# Skematic.net
KiCad netlist of a schematic drawn in EasyEDA
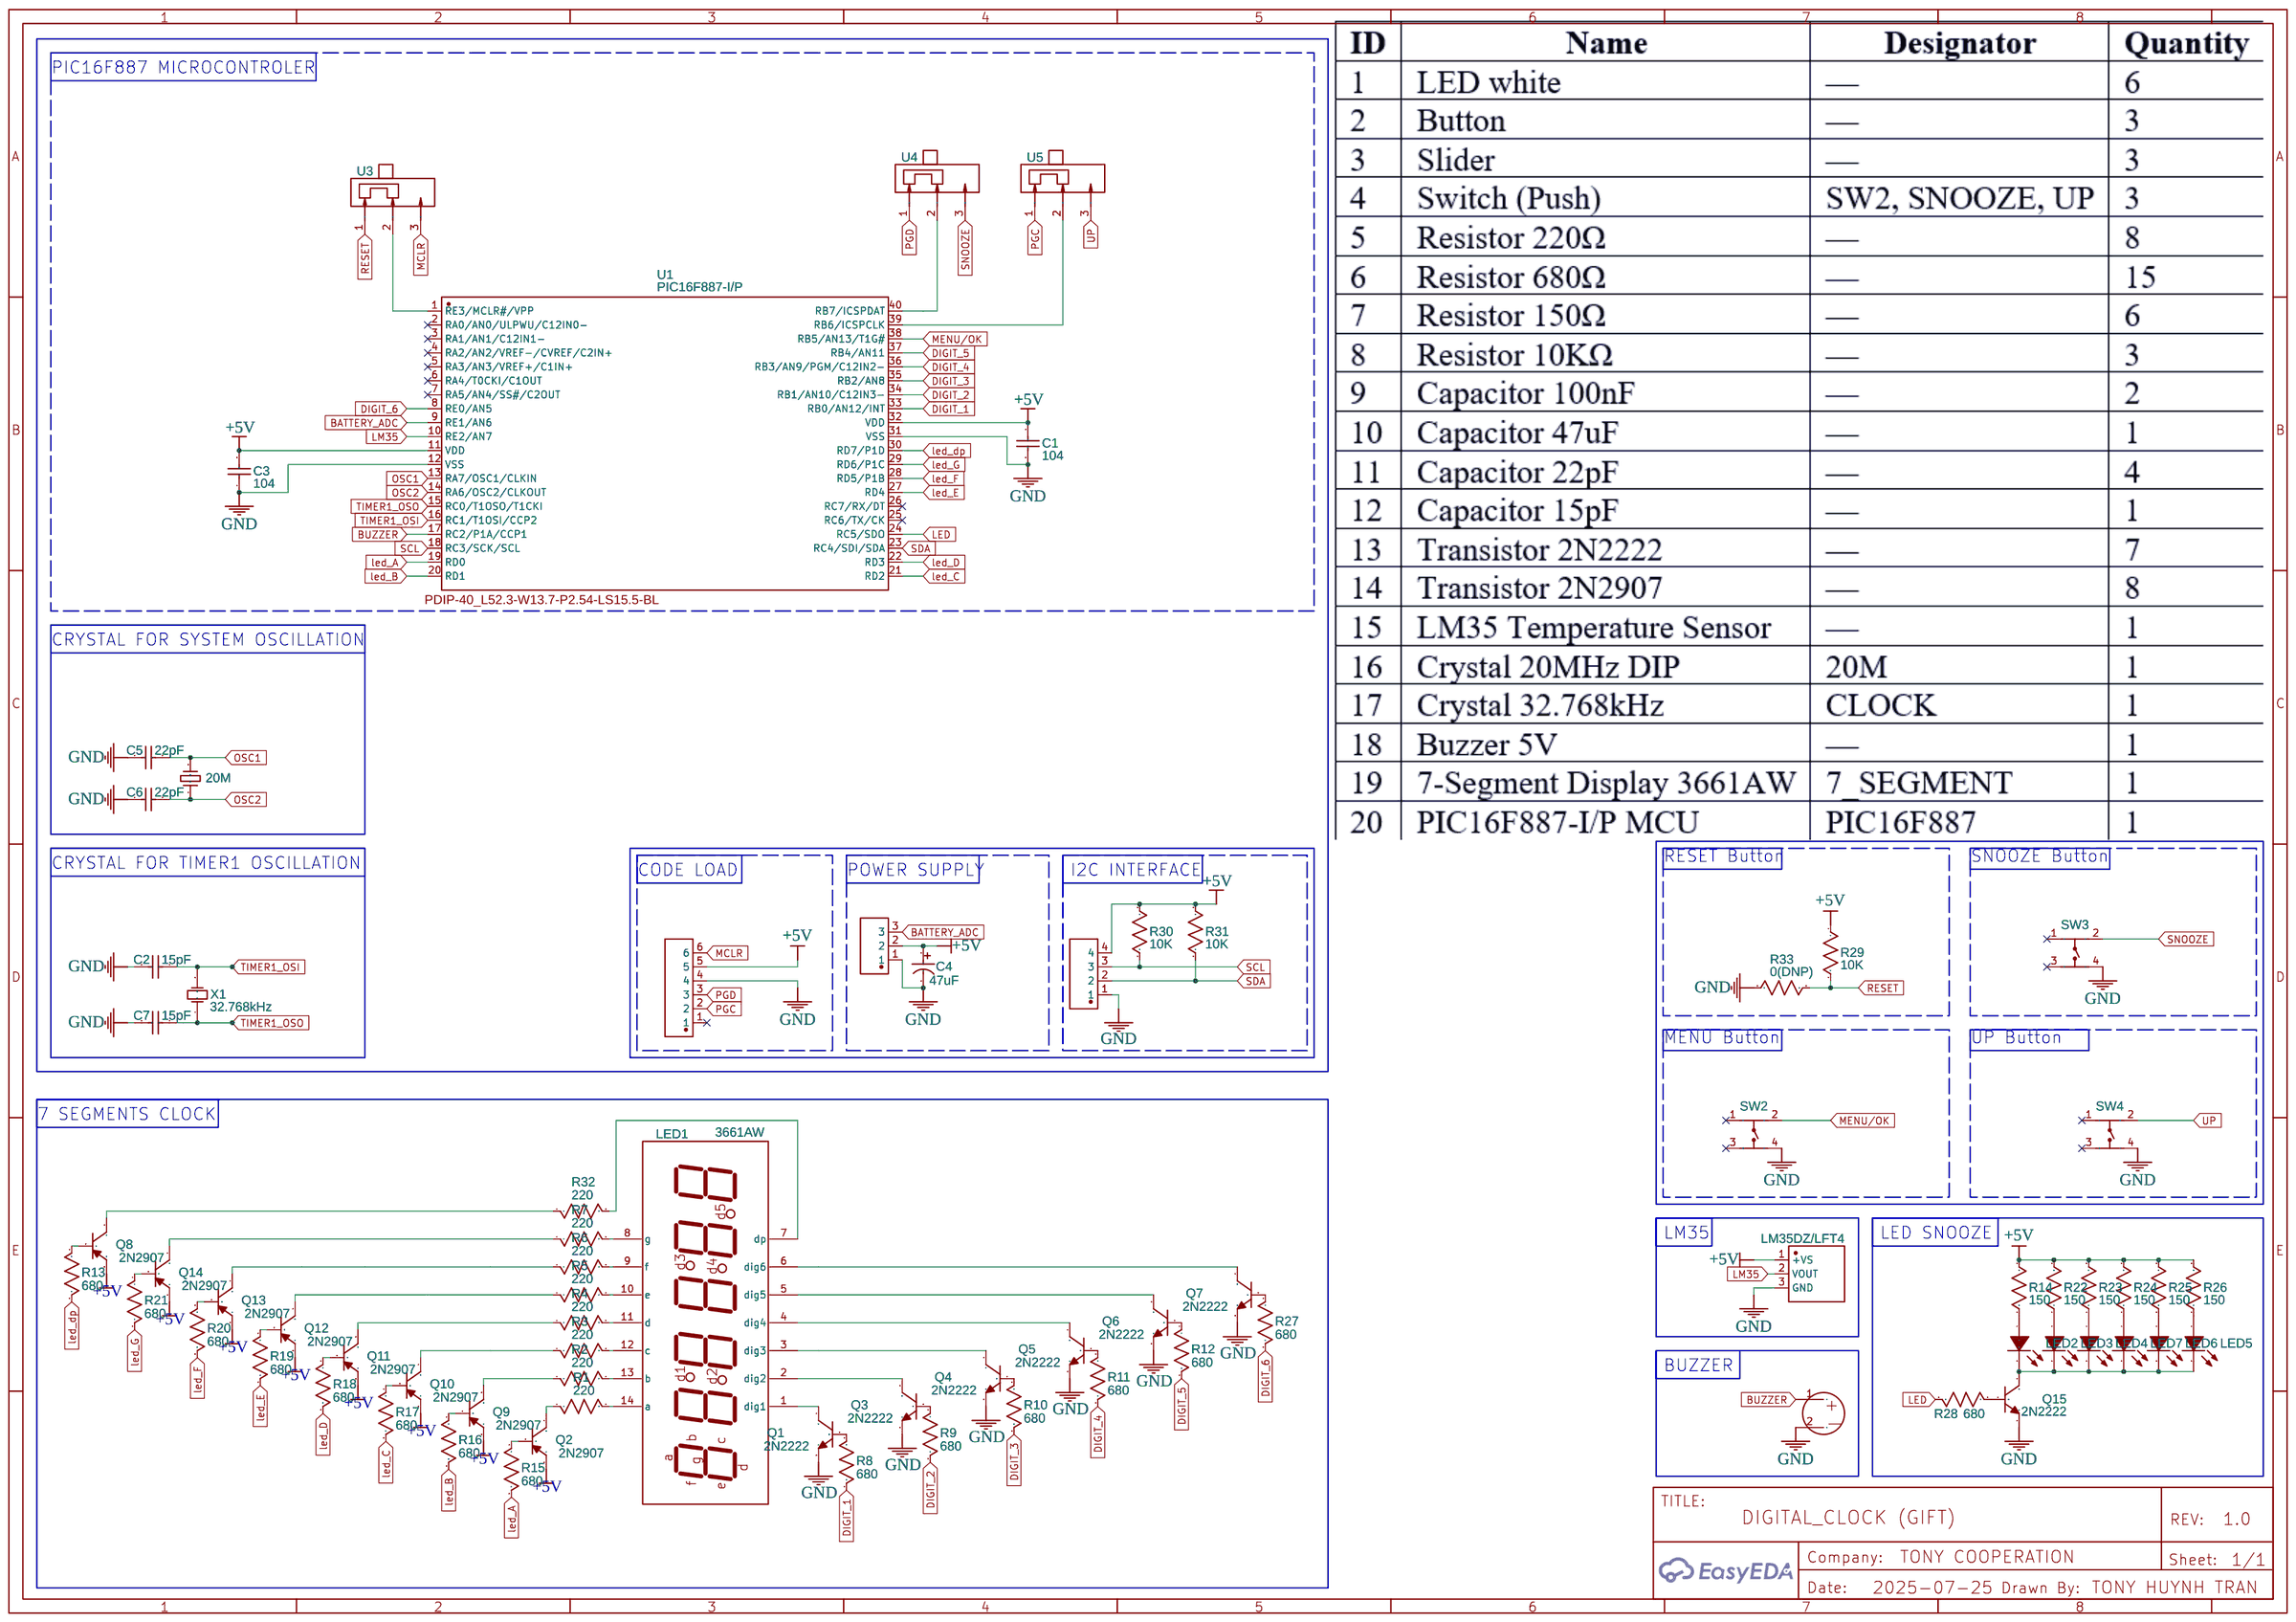
[diagram p0: schematic sheet]

(export (version "E")
  (design (tool "Eeschema 10.0.6"))
  (components
    (comp (ref "20M") (value "Crystal DIP 5.08mm") (libsource (lib "") (part "Crystal DIP 5.08mm")))
    (comp (ref "C1")
      (value "104")
      (fields
        (field (name "Manufacturer Part") "Suppression Capacitor222M/250V")
        (field (name "Manufacturer") "ReliaPro")
      )
      (libsource (lib "") (part "CAP-104"))
    )
    (comp (ref "C2")
      (value "15pF")
      (fields (field (name "Manufacturer Part") "22pf/50V 10%") (field (name "Manufacturer") "ReliaPro"))
      (libsource (lib "") (part "22pF"))
    )
    (comp (ref "C3")
      (value "104")
      (fields
        (field (name "Manufacturer Part") "Suppression Capacitor222M/250V")
        (field (name "Manufacturer") "ReliaPro")
      )
      (libsource (lib "") (part "CAP-104"))
    )
    (comp (ref "C4")
      (value "47uF")
      (fields
        (field (name "Manufacturer Part") "KM108M025G17RR0VH2FP0")
        (field (name "Manufacturer") "CX(承兴)")
      )
      (libsource (lib "") (part "16V 47UF COPY"))
    )
    (comp (ref "C5")
      (value "22pF")
      (fields (field (name "Manufacturer Part") "22pf/50V 10%") (field (name "Manufacturer") "ReliaPro"))
      (libsource (lib "") (part "22pF"))
    )
    (comp (ref "C6")
      (value "22pF")
      (fields (field (name "Manufacturer Part") "22pf/50V 10%") (field (name "Manufacturer") "ReliaPro"))
      (libsource (lib "") (part "22pF"))
    )
    (comp (ref "C7")
      (value "15pF")
      (fields (field (name "Manufacturer Part") "22pf/50V 10%") (field (name "Manufacturer") "ReliaPro"))
      (libsource (lib "") (part "22pF"))
    )
    (comp (ref "H1")
      (value "HC-PZ200-8.7L-1X4PZ")
      (fields
        (field (name "Manufacturer Part") "HC-PZ200-8.7L-1x4PZ")
        (field (name "Manufacturer") "HC(虹成电子)")
      )
      (libsource (lib "") (part "HC-PZ200-8.7L-1X4PZ"))
    )
    (comp (ref "H2")
      (value "HX PZ1.27-1X6P WZ")
      (fields
        (field (name "Manufacturer Part") "HX PZ1.27-1x6P WZ")
        (field (name "Manufacturer") "hanxia(韩下)")
      )
      (libsource (lib "") (part "HX PZ1.27-1X6P WZ"))
    )
    (comp (ref "H3")
      (value "HX PZ2.0-1X3P WZ-AM")
      (fields
        (field (name "Manufacturer Part") "HX PZ2.0-1x3P WZ-AM")
        (field (name "Manufacturer") "hanxia(韩下)")
      )
      (libsource (lib "") (part "HX PZ2.0-1X3P WZ-AM"))
    )
    (comp (ref "LED1")
      (value "3661AW")
      (fields (field (name "Manufacturer Part") "3661A_CLK") (field (name "Manufacturer") "CLee LED Store"))
      (libsource (lib "") (part "3661A_CLK"))
    )
    (comp (ref "LED2")
      (value "LED-TH-5mm_R")
      (fields
        (field (name "Manufacturer Part") "333-2SURD/S530-A3")
        (field (name "Manufacturer") "EVERLIGHT(台湾亿光)")
      )
      (libsource (lib "") (part "LED-TH-5mm_R"))
    )
    (comp (ref "LED3")
      (value "LED-TH-5mm_R")
      (fields
        (field (name "Manufacturer Part") "333-2SURD/S530-A3")
        (field (name "Manufacturer") "EVERLIGHT(台湾亿光)")
      )
      (libsource (lib "") (part "LED-TH-5mm_R"))
    )
    (comp (ref "LED4")
      (value "LED-TH-5mm_R")
      (fields
        (field (name "Manufacturer Part") "333-2SURD/S530-A3")
        (field (name "Manufacturer") "EVERLIGHT(台湾亿光)")
      )
      (libsource (lib "") (part "LED-TH-5mm_R"))
    )
    (comp (ref "LED5")
      (value "LED-TH-5mm_R")
      (fields
        (field (name "Manufacturer Part") "333-2SURD/S530-A3")
        (field (name "Manufacturer") "EVERLIGHT(台湾亿光)")
      )
      (libsource (lib "") (part "LED-TH-5mm_R"))
    )
    (comp (ref "LED6")
      (value "LED-TH-5mm_R")
      (fields
        (field (name "Manufacturer Part") "333-2SURD/S530-A3")
        (field (name "Manufacturer") "EVERLIGHT(台湾亿光)")
      )
      (libsource (lib "") (part "LED-TH-5mm_R"))
    )
    (comp (ref "LED7")
      (value "LED-TH-5mm_R")
      (fields
        (field (name "Manufacturer Part") "333-2SURD/S530-A3")
        (field (name "Manufacturer") "EVERLIGHT(台湾亿光)")
      )
      (libsource (lib "") (part "LED-TH-5mm_R"))
    )
    (comp (ref "Q1")
      (value "2N2222")
      (fields (field (name "Manufacturer Part") "2N2222A") (field (name "Manufacturer") "BLUE ROCKET(蓝箭)"))
      (libsource (lib "") (part "2N2222A"))
    )
    (comp (ref "Q2")
      (value "2N2907")
      (fields (field (name "Manufacturer Part") "2N2907A") (field (name "Manufacturer") "BLUE ROCKET(蓝箭)"))
      (libsource (lib "") (part "2N2907A"))
    )
    (comp (ref "Q3")
      (value "2N2222")
      (fields (field (name "Manufacturer Part") "2N2222A") (field (name "Manufacturer") "BLUE ROCKET(蓝箭)"))
      (libsource (lib "") (part "2N2222A"))
    )
    (comp (ref "Q4")
      (value "2N2222")
      (fields (field (name "Manufacturer Part") "2N2222A") (field (name "Manufacturer") "BLUE ROCKET(蓝箭)"))
      (libsource (lib "") (part "2N2222A"))
    )
    (comp (ref "Q5")
      (value "2N2222")
      (fields (field (name "Manufacturer Part") "2N2222A") (field (name "Manufacturer") "BLUE ROCKET(蓝箭)"))
      (libsource (lib "") (part "2N2222A"))
    )
    (comp (ref "Q6")
      (value "2N2222")
      (fields (field (name "Manufacturer Part") "2N2222A") (field (name "Manufacturer") "BLUE ROCKET(蓝箭)"))
      (libsource (lib "") (part "2N2222A"))
    )
    (comp (ref "Q7")
      (value "2N2222")
      (fields (field (name "Manufacturer Part") "2N2222A") (field (name "Manufacturer") "BLUE ROCKET(蓝箭)"))
      (libsource (lib "") (part "2N2222A"))
    )
    (comp (ref "Q8")
      (value "2N2907")
      (fields (field (name "Manufacturer Part") "2N2907A") (field (name "Manufacturer") "BLUE ROCKET(蓝箭)"))
      (libsource (lib "") (part "2N2907A"))
    )
    (comp (ref "Q9")
      (value "2N2907")
      (fields (field (name "Manufacturer Part") "2N2907A") (field (name "Manufacturer") "BLUE ROCKET(蓝箭)"))
      (libsource (lib "") (part "2N2907A"))
    )
    (comp (ref "Q10")
      (value "2N2907")
      (fields (field (name "Manufacturer Part") "2N2907A") (field (name "Manufacturer") "BLUE ROCKET(蓝箭)"))
      (libsource (lib "") (part "2N2907A"))
    )
    (comp (ref "Q11")
      (value "2N2907")
      (fields (field (name "Manufacturer Part") "2N2907A") (field (name "Manufacturer") "BLUE ROCKET(蓝箭)"))
      (libsource (lib "") (part "2N2907A"))
    )
    (comp (ref "Q12")
      (value "2N2907")
      (fields (field (name "Manufacturer Part") "2N2907A") (field (name "Manufacturer") "BLUE ROCKET(蓝箭)"))
      (libsource (lib "") (part "2N2907A"))
    )
    (comp (ref "Q13")
      (value "2N2907")
      (fields (field (name "Manufacturer Part") "2N2907A") (field (name "Manufacturer") "BLUE ROCKET(蓝箭)"))
      (libsource (lib "") (part "2N2907A"))
    )
    (comp (ref "Q14")
      (value "2N2907")
      (fields (field (name "Manufacturer Part") "2N2907A") (field (name "Manufacturer") "BLUE ROCKET(蓝箭)"))
      (libsource (lib "") (part "2N2907A"))
    )
    (comp (ref "Q15")
      (value "2N2222")
      (fields (field (name "Manufacturer Part") "2N2222A") (field (name "Manufacturer") "BLUE ROCKET(蓝箭)"))
      (libsource (lib "") (part "2N2222A_1"))
    )
    (comp (ref "R1") (value "220") (libsource (lib "") (part "R_AXIAL-0.4_US_3")))
    (comp (ref "R2") (value "220") (libsource (lib "") (part "R_AXIAL-0.4_US_3")))
    (comp (ref "R3") (value "220") (libsource (lib "") (part "R_AXIAL-0.4_US_3")))
    (comp (ref "R4") (value "220") (libsource (lib "") (part "R_AXIAL-0.4_US_3")))
    (comp (ref "R5") (value "220") (libsource (lib "") (part "R_AXIAL-0.4_US_3")))
    (comp (ref "R6") (value "220") (libsource (lib "") (part "R_AXIAL-0.4_US_3")))
    (comp (ref "R7") (value "220") (libsource (lib "") (part "R_AXIAL-0.4_US_3")))
    (comp (ref "R8") (value "680") (libsource (lib "") (part "R_AXIAL-0.4_US_2")))
    (comp (ref "R9") (value "680") (libsource (lib "") (part "R_AXIAL-0.4_US_2")))
    (comp (ref "R10") (value "680") (libsource (lib "") (part "R_AXIAL-0.4_US_2")))
    (comp (ref "R11") (value "680") (libsource (lib "") (part "R_AXIAL-0.4_US_2")))
    (comp (ref "R12") (value "680") (libsource (lib "") (part "R_AXIAL-0.4_US_2")))
    (comp (ref "R13") (value "680") (libsource (lib "") (part "R_AXIAL-0.4_US_2")))
    (comp (ref "R14") (value "150") (libsource (lib "") (part "R_AXIAL-0.4_US_4")))
    (comp (ref "R15") (value "680") (libsource (lib "") (part "R_AXIAL-0.4_US_2")))
    (comp (ref "R16") (value "680") (libsource (lib "") (part "R_AXIAL-0.4_US_2")))
    (comp (ref "R17") (value "680") (libsource (lib "") (part "R_AXIAL-0.4_US_2")))
    (comp (ref "R18") (value "680") (libsource (lib "") (part "R_AXIAL-0.4_US_2")))
    (comp (ref "R19") (value "680") (libsource (lib "") (part "R_AXIAL-0.4_US_2")))
    (comp (ref "R20") (value "680") (libsource (lib "") (part "R_AXIAL-0.4_US_2")))
    (comp (ref "R21") (value "680") (libsource (lib "") (part "R_AXIAL-0.4_US_2")))
    (comp (ref "R22") (value "150") (libsource (lib "") (part "R_AXIAL-0.4_US_4")))
    (comp (ref "R23") (value "150") (libsource (lib "") (part "R_AXIAL-0.4_US_4")))
    (comp (ref "R24") (value "150") (libsource (lib "") (part "R_AXIAL-0.4_US_4")))
    (comp (ref "R25") (value "150") (libsource (lib "") (part "R_AXIAL-0.4_US_4")))
    (comp (ref "R26") (value "150") (libsource (lib "") (part "R_AXIAL-0.4_US_4")))
    (comp (ref "R27") (value "680") (libsource (lib "") (part "R_AXIAL-0.4_US_2")))
    (comp (ref "R28") (value "680") (libsource (lib "") (part "R_AXIAL-0.4_US_1")))
    (comp (ref "R29") (value "10K") (libsource (lib "") (part "R_AXIAL-0.4_US_5")))
    (comp (ref "R30") (value "10K") (libsource (lib "") (part "R_AXIAL-0.4_US_4")))
    (comp (ref "R31") (value "10K") (libsource (lib "") (part "R_AXIAL-0.4_US_4")))
    (comp (ref "R32") (value "220") (libsource (lib "") (part "R_AXIAL-0.4_US_3")))
    (comp (ref "R33") (value "0(DNP)") (libsource (lib "") (part "R_AXIAL-0.4_US")))
    (comp (ref "SW2")
      (value "1")
      (fields
        (field (name "Manufacturer Part") "TS1103S-12x12x10.5DIP")
        (field (name "Manufacturer") "CAX(创都)")
      )
      (libsource (lib "") (part "TS1103S-12X12X10.5DIP"))
    )
    (comp (ref "SW3")
      (value "1")
      (fields
        (field (name "Manufacturer Part") "TS1103S-12x12x10.5DIP")
        (field (name "Manufacturer") "CAX(创都)")
      )
      (libsource (lib "") (part "TS1103S-12X12X10.5DIP"))
    )
    (comp (ref "SW4")
      (value "1")
      (fields
        (field (name "Manufacturer Part") "TS1103S-12x12x10.5DIP")
        (field (name "Manufacturer") "CAX(创都)")
      )
      (libsource (lib "") (part "TS1103S-12X12X10.5DIP"))
    )
    (comp (ref "U1")
      (value "PIC16F887-I/P")
      (fields (field (name "Manufacturer") "MICROCHIP(美国微芯)"))
      (libsource (lib "") (part "PIC16F887-I/P"))
    )
    (comp (ref "U2")
      (value "LM35DZ/LFT4")
      (fields (field (name "Manufacturer") "TI(德州仪器)"))
      (libsource (lib "") (part "LM35DZ/LFT4"))
    )
    (comp (ref "U3")
      (value "SS-12D00-G3")
      (fields (field (name "Manufacturer") "SOFNG(硕方)"))
      (libsource (lib "") (part "SS-12D00-G3"))
    )
    (comp (ref "U4")
      (value "SS-12D00-G3")
      (fields (field (name "Manufacturer") "SOFNG(硕方)"))
      (libsource (lib "") (part "SS-12D00-G3"))
    )
    (comp (ref "U5")
      (value "SS-12D00-G3")
      (fields (field (name "Manufacturer") "SOFNG(硕方)"))
      (libsource (lib "") (part "SS-12D00-G3"))
    )
    (comp (ref "U6") (value "Buzzer 12mm x 5mm") (libsource (lib "") (part "Buzzer 12mm x 5mm")))
    (comp (ref "X1")
      (value "32.768kHz")
      (fields
        (field (name "Manufacturer Part") "Y6OEL89CIC-STUYLC-32.768K")
        (field (name "Manufacturer") "YXC(扬兴晶振)")
      )
      (libsource (lib "") (part "Y6OEL89CIC-STUYLC-32.768K"))
    )
  )
  (nets
    (net (code "1") (name "+5V") (class "Default")
      (node (ref "C1") (pin "2") (pinfunction "2_2") (pintype "input"))
      (node (ref "C3") (pin "2") (pinfunction "2_2") (pintype "input"))
      (node (ref "C4") (pin "1") (pinfunction "1_1") (pintype "input"))
      (node (ref "H1") (pin "4") (pinfunction "4_4") (pintype "unspecified"))
      (node (ref "H2") (pin "5") (pinfunction "5_5") (pintype "unspecified"))
      (node (ref "H3") (pin "2") (pinfunction "2_2") (pintype "unspecified"))
      (node (ref "Q10") (pin "3") (pinfunction "E_3") (pintype "unspecified"))
      (node (ref "Q11") (pin "3") (pinfunction "E_3") (pintype "unspecified"))
      (node (ref "Q12") (pin "3") (pinfunction "E_3") (pintype "unspecified"))
      (node (ref "Q13") (pin "3") (pinfunction "E_3") (pintype "unspecified"))
      (node (ref "Q14") (pin "3") (pinfunction "E_3") (pintype "unspecified"))
      (node (ref "Q2") (pin "3") (pinfunction "E_3") (pintype "unspecified"))
      (node (ref "Q8") (pin "3") (pinfunction "E_3") (pintype "unspecified"))
      (node (ref "Q9") (pin "3") (pinfunction "E_3") (pintype "unspecified"))
      (node (ref "R14") (pin "2") (pinfunction "2_2") (pintype "unspecified"))
      (node (ref "R22") (pin "2") (pinfunction "2_2") (pintype "unspecified"))
      (node (ref "R23") (pin "2") (pinfunction "2_2") (pintype "unspecified"))
      (node (ref "R24") (pin "2") (pinfunction "2_2") (pintype "unspecified"))
      (node (ref "R25") (pin "2") (pinfunction "2_2") (pintype "unspecified"))
      (node (ref "R26") (pin "2") (pinfunction "2_2") (pintype "unspecified"))
      (node (ref "R29") (pin "1") (pinfunction "1_1") (pintype "unspecified"))
      (node (ref "R30") (pin "2") (pinfunction "2_2") (pintype "unspecified"))
      (node (ref "R31") (pin "2") (pinfunction "2_2") (pintype "unspecified"))
      (node (ref "U1") (pin "11") (pinfunction "VDD_11") (pintype "unspecified"))
      (node (ref "U1") (pin "32") (pinfunction "VDD_32") (pintype "unspecified"))
      (node (ref "U2") (pin "1") (pinfunction "+VS_1") (pintype "unspecified"))
    )
    (net (code "2") (name "BATTERY_ADC") (class "Default")
      (node (ref "H3") (pin "3") (pinfunction "3_3") (pintype "unspecified"))
      (node (ref "U1") (pin "9") (pinfunction "RE1/AN6_9") (pintype "unspecified"))
    )
    (net (code "3") (name "BUZZER") (class "Default")
      (node (ref "U1") (pin "17") (pinfunction "RC2/P1A/CCP1_17") (pintype "unspecified"))
      (node (ref "U6") (pin "1") (pinfunction "1_1") (pintype "unspecified"))
    )
    (net (code "4") (name "DIGIT_1") (class "Default")
      (node (ref "R8") (pin "2") (pinfunction "2_2") (pintype "unspecified"))
      (node (ref "U1") (pin "33") (pinfunction "RB0/AN12/INT_33") (pintype "unspecified"))
    )
    (net (code "5") (name "DIGIT_2") (class "Default")
      (node (ref "R9") (pin "2") (pinfunction "2_2") (pintype "unspecified"))
      (node (ref "U1") (pin "34") (pinfunction "RB1/AN10/C12IN3-_34") (pintype "unspecified"))
    )
    (net (code "6") (name "DIGIT_3") (class "Default")
      (node (ref "R10") (pin "2") (pinfunction "2_2") (pintype "unspecified"))
      (node (ref "U1") (pin "35") (pinfunction "RB2/AN8_35") (pintype "unspecified"))
    )
    (net (code "7") (name "DIGIT_4") (class "Default")
      (node (ref "R11") (pin "2") (pinfunction "2_2") (pintype "unspecified"))
      (node (ref "U1") (pin "36") (pinfunction "RB3/AN9/PGM/C12IN2-_36") (pintype "unspecified"))
    )
    (net (code "8") (name "DIGIT_5") (class "Default")
      (node (ref "R12") (pin "2") (pinfunction "2_2") (pintype "unspecified"))
      (node (ref "U1") (pin "37") (pinfunction "RB4/AN11_37") (pintype "unspecified"))
    )
    (net (code "9") (name "DIGIT_6") (class "Default")
      (node (ref "R27") (pin "2") (pinfunction "2_2") (pintype "unspecified"))
      (node (ref "U1") (pin "8") (pinfunction "RE0/AN5_8") (pintype "unspecified"))
    )
    (net (code "10") (name "GND") (class "Default")
      (node (ref "C1") (pin "1") (pinfunction "1_1") (pintype "input"))
      (node (ref "C2") (pin "1") (pinfunction "1_1") (pintype "input"))
      (node (ref "C3") (pin "1") (pinfunction "1_1") (pintype "input"))
      (node (ref "C4") (pin "2") (pinfunction "2_2") (pintype "input"))
      (node (ref "C5") (pin "1") (pinfunction "1_1") (pintype "input"))
      (node (ref "C6") (pin "1") (pinfunction "1_1") (pintype "input"))
      (node (ref "C7") (pin "1") (pinfunction "1_1") (pintype "input"))
      (node (ref "H1") (pin "1") (pinfunction "1_1") (pintype "unspecified"))
      (node (ref "H2") (pin "4") (pinfunction "4_4") (pintype "unspecified"))
      (node (ref "H3") (pin "1") (pinfunction "1_1") (pintype "unspecified"))
      (node (ref "Q1") (pin "3") (pinfunction "E_3") (pintype "unspecified"))
      (node (ref "Q15") (pin "3") (pinfunction "E_3") (pintype "unspecified"))
      (node (ref "Q3") (pin "3") (pinfunction "E_3") (pintype "unspecified"))
      (node (ref "Q4") (pin "3") (pinfunction "E_3") (pintype "unspecified"))
      (node (ref "Q5") (pin "3") (pinfunction "E_3") (pintype "unspecified"))
      (node (ref "Q6") (pin "3") (pinfunction "E_3") (pintype "unspecified"))
      (node (ref "Q7") (pin "3") (pinfunction "E_3") (pintype "unspecified"))
      (node (ref "R33") (pin "1") (pinfunction "1_1") (pintype "unspecified"))
      (node (ref "SW2") (pin "4") (pinfunction "4_4") (pintype "unspecified"))
      (node (ref "SW3") (pin "4") (pinfunction "4_4") (pintype "unspecified"))
      (node (ref "SW4") (pin "4") (pinfunction "4_4") (pintype "unspecified"))
      (node (ref "U1") (pin "12") (pinfunction "VSS_12") (pintype "unspecified"))
      (node (ref "U1") (pin "31") (pinfunction "VSS_31") (pintype "unspecified"))
      (node (ref "U2") (pin "3") (pinfunction "GND_3") (pintype "unspecified"))
      (node (ref "U6") (pin "2") (pinfunction "2_2") (pintype "unspecified"))
    )
    (net (code "11") (name "LED") (class "Default")
      (node (ref "R28") (pin "2") (pinfunction "2_2") (pintype "unspecified"))
      (node (ref "U1") (pin "24") (pinfunction "RC5/SDO_24") (pintype "unspecified"))
    )
    (net (code "12") (name "LM35") (class "Default")
      (node (ref "U1") (pin "10") (pinfunction "RE2/AN7_10") (pintype "unspecified"))
      (node (ref "U2") (pin "2") (pinfunction "VOUT_2") (pintype "unspecified"))
    )
    (net (code "13") (name "MCLR") (class "Default")
      (node (ref "H2") (pin "6") (pinfunction "6_6") (pintype "unspecified"))
      (node (ref "U3") (pin "3") (pinfunction "3_3") (pintype "unspecified"))
    )
    (net (code "14") (name "MENU{slash}OK") (class "Default")
      (node (ref "SW2") (pin "2") (pinfunction "2_2") (pintype "unspecified"))
      (node (ref "U1") (pin "38") (pinfunction "RB5/AN13/T1G#_38") (pintype "unspecified"))
    )
    (net (code "15") (name "Net-(LED1-a)") (class "Default")
      (node (ref "LED1") (pin "14") (pinfunction "a_14") (pintype "input"))
      (node (ref "R1") (pin "2") (pinfunction "2_2") (pintype "unspecified"))
    )
    (net (code "16") (name "Net-(LED1-b)") (class "Default")
      (node (ref "LED1") (pin "13") (pinfunction "b_13") (pintype "input"))
      (node (ref "R2") (pin "2") (pinfunction "2_2") (pintype "unspecified"))
    )
    (net (code "17") (name "Net-(LED1-c)") (class "Default")
      (node (ref "LED1") (pin "12") (pinfunction "c_12") (pintype "input"))
      (node (ref "R3") (pin "2") (pinfunction "2_2") (pintype "unspecified"))
    )
    (net (code "18") (name "Net-(LED1-d)") (class "Default")
      (node (ref "LED1") (pin "11") (pinfunction "d_11") (pintype "input"))
      (node (ref "R4") (pin "2") (pinfunction "2_2") (pintype "unspecified"))
    )
    (net (code "19") (name "Net-(LED1-dig1)") (class "Default")
      (node (ref "LED1") (pin "1") (pinfunction "dig1_1") (pintype "input"))
      (node (ref "Q1") (pin "1") (pinfunction "C_1") (pintype "unspecified"))
    )
    (net (code "20") (name "Net-(LED1-dig2)") (class "Default")
      (node (ref "LED1") (pin "2") (pinfunction "dig2_2") (pintype "input"))
      (node (ref "Q3") (pin "1") (pinfunction "C_1") (pintype "unspecified"))
    )
    (net (code "21") (name "Net-(LED1-dig3)") (class "Default")
      (node (ref "LED1") (pin "3") (pinfunction "dig3_3") (pintype "input"))
      (node (ref "Q4") (pin "1") (pinfunction "C_1") (pintype "unspecified"))
    )
    (net (code "22") (name "Net-(LED1-dig4)") (class "Default")
      (node (ref "LED1") (pin "4") (pinfunction "dig4_4") (pintype "input"))
      (node (ref "Q5") (pin "1") (pinfunction "C_1") (pintype "unspecified"))
    )
    (net (code "23") (name "Net-(LED1-dig5)") (class "Default")
      (node (ref "LED1") (pin "5") (pinfunction "dig5_5") (pintype "input"))
      (node (ref "Q6") (pin "1") (pinfunction "C_1") (pintype "unspecified"))
    )
    (net (code "24") (name "Net-(LED1-dig6)") (class "Default")
      (node (ref "LED1") (pin "6") (pinfunction "dig6_6") (pintype "input"))
      (node (ref "Q7") (pin "1") (pinfunction "C_1") (pintype "unspecified"))
    )
    (net (code "25") (name "Net-(LED1-dp)") (class "Default")
      (node (ref "LED1") (pin "7") (pinfunction "dp_7") (pintype "input"))
      (node (ref "R32") (pin "2") (pinfunction "2_2") (pintype "unspecified"))
    )
    (net (code "26") (name "Net-(LED1-e)") (class "Default")
      (node (ref "LED1") (pin "10") (pinfunction "e_10") (pintype "input"))
      (node (ref "R5") (pin "2") (pinfunction "2_2") (pintype "unspecified"))
    )
    (net (code "27") (name "Net-(LED1-f)") (class "Default")
      (node (ref "LED1") (pin "9") (pinfunction "f_9") (pintype "input"))
      (node (ref "R6") (pin "2") (pinfunction "2_2") (pintype "unspecified"))
    )
    (net (code "28") (name "Net-(LED1-g)") (class "Default")
      (node (ref "LED1") (pin "8") (pinfunction "g_8") (pintype "input"))
      (node (ref "R7") (pin "2") (pinfunction "2_2") (pintype "unspecified"))
    )
    (net (code "29") (name "Net-(LED2-Pad1)") (class "Default")
      (node (ref "LED2") (pin "1") (pinfunction "1_1") (pintype "unspecified"))
      (node (ref "R14") (pin "1") (pinfunction "1_1") (pintype "unspecified"))
    )
    (net (code "30") (name "Net-(LED3-Pad1)") (class "Default")
      (node (ref "LED3") (pin "1") (pinfunction "1_1") (pintype "unspecified"))
      (node (ref "R22") (pin "1") (pinfunction "1_1") (pintype "unspecified"))
    )
    (net (code "31") (name "Net-(LED4-Pad1)") (class "Default")
      (node (ref "LED4") (pin "1") (pinfunction "1_1") (pintype "unspecified"))
      (node (ref "R23") (pin "1") (pinfunction "1_1") (pintype "unspecified"))
    )
    (net (code "32") (name "Net-(LED5-Pad1)") (class "Default")
      (node (ref "LED5") (pin "1") (pinfunction "1_1") (pintype "unspecified"))
      (node (ref "R26") (pin "1") (pinfunction "1_1") (pintype "unspecified"))
    )
    (net (code "33") (name "Net-(LED6-Pad1)") (class "Default")
      (node (ref "LED6") (pin "1") (pinfunction "1_1") (pintype "unspecified"))
      (node (ref "R25") (pin "1") (pinfunction "1_1") (pintype "unspecified"))
    )
    (net (code "34") (name "Net-(LED7-Pad1)") (class "Default")
      (node (ref "LED7") (pin "1") (pinfunction "1_1") (pintype "unspecified"))
      (node (ref "R24") (pin "1") (pinfunction "1_1") (pintype "unspecified"))
    )
    (net (code "35") (name "Net-(Q1-B)") (class "Default")
      (node (ref "Q1") (pin "2") (pinfunction "B_2") (pintype "unspecified"))
      (node (ref "R8") (pin "1") (pinfunction "1_1") (pintype "unspecified"))
    )
    (net (code "36") (name "Net-(Q2-B)") (class "Default")
      (node (ref "Q2") (pin "2") (pinfunction "B_2") (pintype "unspecified"))
      (node (ref "R15") (pin "1") (pinfunction "1_1") (pintype "unspecified"))
    )
    (net (code "37") (name "Net-(Q2-C)") (class "Default")
      (node (ref "Q2") (pin "1") (pinfunction "C_1") (pintype "unspecified"))
      (node (ref "R1") (pin "1") (pinfunction "1_1") (pintype "unspecified"))
    )
    (net (code "38") (name "Net-(Q3-B)") (class "Default")
      (node (ref "Q3") (pin "2") (pinfunction "B_2") (pintype "unspecified"))
      (node (ref "R9") (pin "1") (pinfunction "1_1") (pintype "unspecified"))
    )
    (net (code "39") (name "Net-(Q4-B)") (class "Default")
      (node (ref "Q4") (pin "2") (pinfunction "B_2") (pintype "unspecified"))
      (node (ref "R10") (pin "1") (pinfunction "1_1") (pintype "unspecified"))
    )
    (net (code "40") (name "Net-(Q5-B)") (class "Default")
      (node (ref "Q5") (pin "2") (pinfunction "B_2") (pintype "unspecified"))
      (node (ref "R11") (pin "1") (pinfunction "1_1") (pintype "unspecified"))
    )
    (net (code "41") (name "Net-(Q6-B)") (class "Default")
      (node (ref "Q6") (pin "2") (pinfunction "B_2") (pintype "unspecified"))
      (node (ref "R12") (pin "1") (pinfunction "1_1") (pintype "unspecified"))
    )
    (net (code "42") (name "Net-(Q7-B)") (class "Default")
      (node (ref "Q7") (pin "2") (pinfunction "B_2") (pintype "unspecified"))
      (node (ref "R27") (pin "1") (pinfunction "1_1") (pintype "unspecified"))
    )
    (net (code "43") (name "Net-(Q8-B)") (class "Default")
      (node (ref "Q8") (pin "2") (pinfunction "B_2") (pintype "unspecified"))
      (node (ref "R13") (pin "1") (pinfunction "1_1") (pintype "unspecified"))
    )
    (net (code "44") (name "Net-(Q8-C)") (class "Default")
      (node (ref "Q8") (pin "1") (pinfunction "C_1") (pintype "unspecified"))
      (node (ref "R32") (pin "1") (pinfunction "1_1") (pintype "unspecified"))
    )
    (net (code "45") (name "Net-(Q9-B)") (class "Default")
      (node (ref "Q9") (pin "2") (pinfunction "B_2") (pintype "unspecified"))
      (node (ref "R16") (pin "1") (pinfunction "1_1") (pintype "unspecified"))
    )
    (net (code "46") (name "Net-(Q9-C)") (class "Default")
      (node (ref "Q9") (pin "1") (pinfunction "C_1") (pintype "unspecified"))
      (node (ref "R2") (pin "1") (pinfunction "1_1") (pintype "unspecified"))
    )
    (net (code "47") (name "Net-(Q10-B)") (class "Default")
      (node (ref "Q10") (pin "2") (pinfunction "B_2") (pintype "unspecified"))
      (node (ref "R17") (pin "1") (pinfunction "1_1") (pintype "unspecified"))
    )
    (net (code "48") (name "Net-(Q10-C)") (class "Default")
      (node (ref "Q10") (pin "1") (pinfunction "C_1") (pintype "unspecified"))
      (node (ref "R3") (pin "1") (pinfunction "1_1") (pintype "unspecified"))
    )
    (net (code "49") (name "Net-(Q11-B)") (class "Default")
      (node (ref "Q11") (pin "2") (pinfunction "B_2") (pintype "unspecified"))
      (node (ref "R18") (pin "1") (pinfunction "1_1") (pintype "unspecified"))
    )
    (net (code "50") (name "Net-(Q11-C)") (class "Default")
      (node (ref "Q11") (pin "1") (pinfunction "C_1") (pintype "unspecified"))
      (node (ref "R4") (pin "1") (pinfunction "1_1") (pintype "unspecified"))
    )
    (net (code "51") (name "Net-(Q12-B)") (class "Default")
      (node (ref "Q12") (pin "2") (pinfunction "B_2") (pintype "unspecified"))
      (node (ref "R19") (pin "1") (pinfunction "1_1") (pintype "unspecified"))
    )
    (net (code "52") (name "Net-(Q12-C)") (class "Default")
      (node (ref "Q12") (pin "1") (pinfunction "C_1") (pintype "unspecified"))
      (node (ref "R5") (pin "1") (pinfunction "1_1") (pintype "unspecified"))
    )
    (net (code "53") (name "Net-(Q13-B)") (class "Default")
      (node (ref "Q13") (pin "2") (pinfunction "B_2") (pintype "unspecified"))
      (node (ref "R20") (pin "1") (pinfunction "1_1") (pintype "unspecified"))
    )
    (net (code "54") (name "Net-(Q13-C)") (class "Default")
      (node (ref "Q13") (pin "1") (pinfunction "C_1") (pintype "unspecified"))
      (node (ref "R6") (pin "1") (pinfunction "1_1") (pintype "unspecified"))
    )
    (net (code "55") (name "Net-(Q14-B)") (class "Default")
      (node (ref "Q14") (pin "2") (pinfunction "B_2") (pintype "unspecified"))
      (node (ref "R21") (pin "1") (pinfunction "1_1") (pintype "unspecified"))
    )
    (net (code "56") (name "Net-(Q14-C)") (class "Default")
      (node (ref "Q14") (pin "1") (pinfunction "C_1") (pintype "unspecified"))
      (node (ref "R7") (pin "1") (pinfunction "1_1") (pintype "unspecified"))
    )
    (net (code "57") (name "Net-(Q15-B)") (class "Default")
      (node (ref "Q15") (pin "2") (pinfunction "B_2") (pintype "unspecified"))
      (node (ref "R28") (pin "1") (pinfunction "1_1") (pintype "unspecified"))
    )
    (net (code "58") (name "Net-(Q15-C)") (class "Default")
      (node (ref "LED2") (pin "2") (pinfunction "2_2") (pintype "unspecified"))
      (node (ref "LED3") (pin "2") (pinfunction "2_2") (pintype "unspecified"))
      (node (ref "LED4") (pin "2") (pinfunction "2_2") (pintype "unspecified"))
      (node (ref "LED5") (pin "2") (pinfunction "2_2") (pintype "unspecified"))
      (node (ref "LED6") (pin "2") (pinfunction "2_2") (pintype "unspecified"))
      (node (ref "LED7") (pin "2") (pinfunction "2_2") (pintype "unspecified"))
      (node (ref "Q15") (pin "1") (pinfunction "C_1") (pintype "unspecified"))
    )
    (net (code "59") (name "Net-(U1-RB6{slash}ICSPCLK)") (class "Default")
      (node (ref "U1") (pin "39") (pinfunction "RB6/ICSPCLK_39") (pintype "unspecified"))
      (node (ref "U5") (pin "2") (pinfunction "2_2") (pintype "unspecified"))
    )
    (net (code "60") (name "Net-(U1-RB7{slash}ICSPDAT)") (class "Default")
      (node (ref "U1") (pin "40") (pinfunction "RB7/ICSPDAT_40") (pintype "unspecified"))
      (node (ref "U4") (pin "2") (pinfunction "2_2") (pintype "unspecified"))
    )
    (net (code "61") (name "Net-(U1-RE3{slash}MCLR#{slash}VPP)") (class "Default")
      (node (ref "U1") (pin "1") (pinfunction "RE3/MCLR#/VPP_1") (pintype "unspecified"))
      (node (ref "U3") (pin "2") (pinfunction "2_2") (pintype "unspecified"))
    )
    (net (code "62") (name "OSC1") (class "Default")
      (node (ref "20M") (pin "1") (pinfunction "1_1") (pintype "unspecified"))
      (node (ref "C5") (pin "2") (pinfunction "2_2") (pintype "input"))
      (node (ref "U1") (pin "13") (pinfunction "RA7/OSC1/CLKIN_13") (pintype "unspecified"))
    )
    (net (code "63") (name "OSC2") (class "Default")
      (node (ref "20M") (pin "2") (pinfunction "2_2") (pintype "unspecified"))
      (node (ref "C6") (pin "2") (pinfunction "2_2") (pintype "input"))
      (node (ref "U1") (pin "14") (pinfunction "RA6/OSC2/CLKOUT_14") (pintype "unspecified"))
    )
    (net (code "64") (name "PGC") (class "Default")
      (node (ref "H2") (pin "2") (pinfunction "2_2") (pintype "unspecified"))
      (node (ref "U5") (pin "1") (pinfunction "1_1") (pintype "unspecified"))
    )
    (net (code "65") (name "PGD") (class "Default")
      (node (ref "H2") (pin "3") (pinfunction "3_3") (pintype "unspecified"))
      (node (ref "U4") (pin "1") (pinfunction "1_1") (pintype "unspecified"))
    )
    (net (code "66") (name "RESET") (class "Default")
      (node (ref "R29") (pin "2") (pinfunction "2_2") (pintype "unspecified"))
      (node (ref "R33") (pin "2") (pinfunction "2_2") (pintype "unspecified"))
      (node (ref "U3") (pin "1") (pinfunction "1_1") (pintype "unspecified"))
    )
    (net (code "67") (name "SCL") (class "Default")
      (node (ref "H1") (pin "3") (pinfunction "3_3") (pintype "unspecified"))
      (node (ref "R30") (pin "1") (pinfunction "1_1") (pintype "unspecified"))
      (node (ref "U1") (pin "18") (pinfunction "RC3/SCK/SCL_18") (pintype "unspecified"))
    )
    (net (code "68") (name "SDA") (class "Default")
      (node (ref "H1") (pin "2") (pinfunction "2_2") (pintype "unspecified"))
      (node (ref "R31") (pin "1") (pinfunction "1_1") (pintype "unspecified"))
      (node (ref "U1") (pin "23") (pinfunction "RC4/SDI/SDA_23") (pintype "unspecified"))
    )
    (net (code "69") (name "SNOOZE") (class "Default")
      (node (ref "SW3") (pin "2") (pinfunction "2_2") (pintype "unspecified"))
      (node (ref "U4") (pin "3") (pinfunction "3_3") (pintype "unspecified"))
    )
    (net (code "70") (name "TIMER1_OSI") (class "Default")
      (node (ref "C2") (pin "2") (pinfunction "2_2") (pintype "input"))
      (node (ref "U1") (pin "16") (pinfunction "RC1/T1OSI/CCP2_16") (pintype "unspecified"))
      (node (ref "X1") (pin "2") (pinfunction "OSC2_2") (pintype "unspecified"))
    )
    (net (code "71") (name "TIMER1_OSO") (class "Default")
      (node (ref "C7") (pin "2") (pinfunction "2_2") (pintype "input"))
      (node (ref "U1") (pin "15") (pinfunction "RC0/T1OSO/T1CKI_15") (pintype "unspecified"))
      (node (ref "X1") (pin "1") (pinfunction "OSC1_1") (pintype "unspecified"))
    )
    (net (code "72") (name "UP") (class "Default")
      (node (ref "SW4") (pin "2") (pinfunction "2_2") (pintype "unspecified"))
      (node (ref "U5") (pin "3") (pinfunction "3_3") (pintype "unspecified"))
    )
    (net (code "73") (name "led_A") (class "Default")
      (node (ref "R15") (pin "2") (pinfunction "2_2") (pintype "unspecified"))
      (node (ref "U1") (pin "19") (pinfunction "RD0_19") (pintype "unspecified"))
    )
    (net (code "74") (name "led_B") (class "Default")
      (node (ref "R16") (pin "2") (pinfunction "2_2") (pintype "unspecified"))
      (node (ref "U1") (pin "20") (pinfunction "RD1_20") (pintype "unspecified"))
    )
    (net (code "75") (name "led_C") (class "Default")
      (node (ref "R17") (pin "2") (pinfunction "2_2") (pintype "unspecified"))
      (node (ref "U1") (pin "21") (pinfunction "RD2_21") (pintype "unspecified"))
    )
    (net (code "76") (name "led_D") (class "Default")
      (node (ref "R18") (pin "2") (pinfunction "2_2") (pintype "unspecified"))
      (node (ref "U1") (pin "22") (pinfunction "RD3_22") (pintype "unspecified"))
    )
    (net (code "77") (name "led_E") (class "Default")
      (node (ref "R19") (pin "2") (pinfunction "2_2") (pintype "unspecified"))
      (node (ref "U1") (pin "27") (pinfunction "RD4_27") (pintype "unspecified"))
    )
    (net (code "78") (name "led_F") (class "Default")
      (node (ref "R20") (pin "2") (pinfunction "2_2") (pintype "unspecified"))
      (node (ref "U1") (pin "28") (pinfunction "RD5/P1B_28") (pintype "unspecified"))
    )
    (net (code "79") (name "led_G") (class "Default")
      (node (ref "R21") (pin "2") (pinfunction "2_2") (pintype "unspecified"))
      (node (ref "U1") (pin "29") (pinfunction "RD6/P1C_29") (pintype "unspecified"))
    )
    (net (code "80") (name "led_dp") (class "Default")
      (node (ref "R13") (pin "2") (pinfunction "2_2") (pintype "unspecified"))
      (node (ref "U1") (pin "30") (pinfunction "RD7/P1D_30") (pintype "unspecified"))
    )
    (net (code "81") (name "unconnected-(H2-Pad1)") (class "Default")
      (node (ref "H2") (pin "1") (pinfunction "1_1") (pintype "unspecified+no_connect"))
    )
    (net (code "82") (name "unconnected-(SW2-Pad1)") (class "Default")
      (node (ref "SW2") (pin "1") (pinfunction "1_1") (pintype "unspecified+no_connect"))
    )
    (net (code "83") (name "unconnected-(SW2-Pad3)") (class "Default")
      (node (ref "SW2") (pin "3") (pinfunction "3_3") (pintype "unspecified+no_connect"))
    )
    (net (code "84") (name "unconnected-(SW3-Pad1)") (class "Default")
      (node (ref "SW3") (pin "1") (pinfunction "1_1") (pintype "unspecified+no_connect"))
    )
    (net (code "85") (name "unconnected-(SW3-Pad3)") (class "Default")
      (node (ref "SW3") (pin "3") (pinfunction "3_3") (pintype "unspecified+no_connect"))
    )
    (net (code "86") (name "unconnected-(SW4-Pad1)") (class "Default")
      (node (ref "SW4") (pin "1") (pinfunction "1_1") (pintype "unspecified+no_connect"))
    )
    (net (code "87") (name "unconnected-(SW4-Pad3)") (class "Default")
      (node (ref "SW4") (pin "3") (pinfunction "3_3") (pintype "unspecified+no_connect"))
    )
    (net (code "88") (name "unconnected-(U1-RA0{slash}AN0{slash}ULPWU{slash}C12IN0--Pad2)") (class "Default")
      (node (ref "U1") (pin "2") (pinfunction "RA0/AN0/ULPWU/C12IN0-_2") (pintype "unspecified+no_connect"))
    )
    (net (code "89") (name "unconnected-(U1-RA1{slash}AN1{slash}C12IN1--Pad3)") (class "Default")
      (node (ref "U1") (pin "3") (pinfunction "RA1/AN1/C12IN1-_3") (pintype "unspecified+no_connect"))
    )
    (net (code "90") (name "unconnected-(U1-RA2{slash}AN2{slash}VREF-{slash}CVREF{slash}C2IN+-Pad4)") (class "Default")
      (node (ref "U1") (pin "4") (pinfunction "RA2/AN2/VREF-/CVREF/C2IN+_4") (pintype "unspecified+no_connect"))
    )
    (net (code "91") (name "unconnected-(U1-RA3{slash}AN3{slash}VREF+{slash}C1IN+-Pad5)") (class "Default")
      (node (ref "U1") (pin "5") (pinfunction "RA3/AN3/VREF+/C1IN+_5") (pintype "unspecified+no_connect"))
    )
    (net (code "92") (name "unconnected-(U1-RA4{slash}T0CKI{slash}C1OUT-Pad6)") (class "Default")
      (node (ref "U1") (pin "6") (pinfunction "RA4/T0CKI/C1OUT_6") (pintype "unspecified+no_connect"))
    )
    (net (code "93") (name "unconnected-(U1-RA5{slash}AN4{slash}SS#{slash}C2OUT-Pad7)") (class "Default")
      (node (ref "U1") (pin "7") (pinfunction "RA5/AN4/SS#/C2OUT_7") (pintype "unspecified+no_connect"))
    )
    (net (code "94") (name "unconnected-(U1-RC6{slash}TX{slash}CK-Pad25)") (class "Default")
      (node (ref "U1") (pin "25") (pinfunction "RC6/TX/CK_25") (pintype "unspecified+no_connect"))
    )
    (net (code "95") (name "unconnected-(U1-RC7{slash}RX{slash}DT-Pad26)") (class "Default")
      (node (ref "U1") (pin "26") (pinfunction "RC7/RX/DT_26") (pintype "unspecified+no_connect"))
    )
  )
)
